# Optic_PWM.net
KiCad netlist of a schematic drawn in Altium Designer
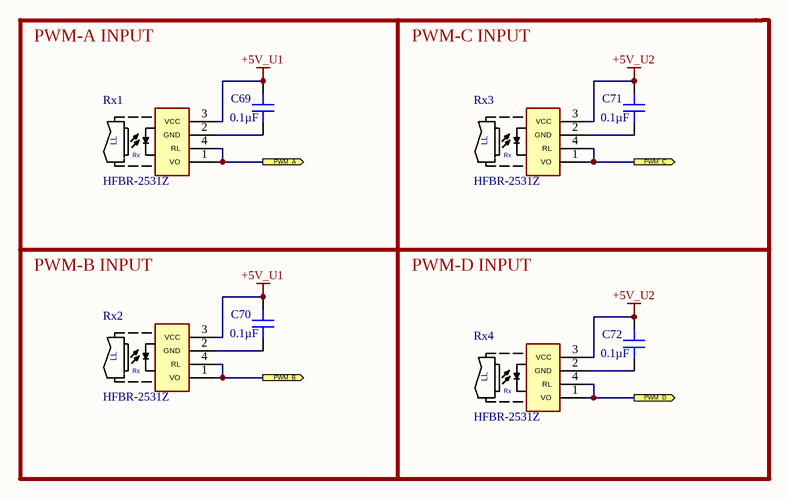
[diagram p0: Optic_PWM.SchDoc]

(export (version "E")
  (design (tool "Eeschema 10.0.6"))
  (components
    (comp (ref "C69")
      (value "0.1µF")
      (footprint "CAP 0603_1608")
      (description "CAP CER 0.1UF 50V X7R 0603")
      (fields (field (name "PART NUMBER") "C0603C104M5RACTU") (field (name "MANUFACTURER") "KEMET"))
      (libsource (lib "Celestial Altium Library - altium_library") (part "Capacitor"))
    )
    (comp (ref "C70")
      (value "0.1µF")
      (footprint "CAP 0603_1608")
      (description "CAP CER 0.1UF 50V X7R 0603")
      (fields (field (name "PART NUMBER") "C0603C104M5RACTU") (field (name "MANUFACTURER") "KEMET"))
      (libsource (lib "Celestial Altium Library - altium_library") (part "Capacitor"))
    )
    (comp (ref "C71")
      (value "0.1µF")
      (footprint "CAP 0603_1608")
      (description "CAP CER 0.1UF 50V X7R 0603")
      (fields (field (name "PART NUMBER") "C0603C104M5RACTU") (field (name "MANUFACTURER") "KEMET"))
      (libsource (lib "Celestial Altium Library - altium_library") (part "Capacitor"))
    )
    (comp (ref "C72")
      (value "0.1µF")
      (footprint "CAP 0603_1608")
      (description "CAP CER 0.1UF 50V X7R 0603")
      (fields (field (name "PART NUMBER") "C0603C104M5RACTU") (field (name "MANUFACTURER") "KEMET"))
      (libsource (lib "Celestial Altium Library - altium_library") (part "Capacitor"))
    )
    (comp (ref "Rx1")
      (value "HFBR-2531Z")
      (footprint "HFBR-15X1V")
      (description "RX Optical Fiber 5MBd 6-Pin")
      (fields (field (name "MANUFACTURER") "Broadcom Avago"))
      (libsource (lib "KasengLIb") (part "HFBR-2531Z"))
    )
    (comp (ref "Rx2")
      (value "HFBR-2531Z")
      (footprint "HFBR-15X1V")
      (description "RX Optical Fiber 5MBd 6-Pin")
      (fields (field (name "MANUFACTURER") "Broadcom Avago"))
      (libsource (lib "KasengLIb") (part "HFBR-2531Z"))
    )
    (comp (ref "Rx3")
      (value "HFBR-2531Z")
      (footprint "HFBR-15X1V")
      (description "RX Optical Fiber 5MBd 6-Pin")
      (fields (field (name "MANUFACTURER") "Broadcom Avago"))
      (libsource (lib "KasengLIb") (part "HFBR-2531Z"))
    )
    (comp (ref "Rx4")
      (value "HFBR-2531Z")
      (footprint "HFBR-15X1V")
      (description "RX Optical Fiber 5MBd 6-Pin")
      (fields (field (name "MANUFACTURER") "Broadcom Avago"))
      (libsource (lib "KasengLIb") (part "HFBR-2531Z"))
    )
  )
  (nets
    (net (code "1") (name "+5V_U1") (class "Default")
      (node (ref "C69") (pin "2") (pinfunction "2_2") (pintype "passive"))
      (node (ref "C70") (pin "2") (pinfunction "2_2") (pintype "passive"))
      (node (ref "Rx1") (pin "3") (pinfunction "VCC_3") (pintype "passive"))
      (node (ref "Rx2") (pin "3") (pinfunction "VCC_3") (pintype "passive"))
    )
    (net (code "2") (name "+5V_U2") (class "Default")
      (node (ref "C71") (pin "2") (pinfunction "2_2") (pintype "passive"))
      (node (ref "C72") (pin "2") (pinfunction "2_2") (pintype "passive"))
      (node (ref "Rx3") (pin "3") (pinfunction "VCC_3") (pintype "passive"))
      (node (ref "Rx4") (pin "3") (pinfunction "VCC_3") (pintype "passive"))
    )
    (net (code "3") (name "/PWM_A") (class "Default")
      (node (ref "Rx1") (pin "1") (pinfunction "VO_1") (pintype "passive"))
      (node (ref "Rx1") (pin "4") (pinfunction "RL_4") (pintype "passive"))
    )
    (net (code "4") (name "/PWM_B") (class "Default")
      (node (ref "Rx2") (pin "1") (pinfunction "VO_1") (pintype "passive"))
      (node (ref "Rx2") (pin "4") (pinfunction "RL_4") (pintype "passive"))
    )
    (net (code "5") (name "/PWM_C") (class "Default")
      (node (ref "Rx3") (pin "1") (pinfunction "VO_1") (pintype "passive"))
      (node (ref "Rx3") (pin "4") (pinfunction "RL_4") (pintype "passive"))
    )
    (net (code "6") (name "/PWM_D") (class "Default")
      (node (ref "Rx4") (pin "1") (pinfunction "VO_1") (pintype "passive"))
      (node (ref "Rx4") (pin "4") (pinfunction "RL_4") (pintype "passive"))
    )
    (net (code "7") (name "Net-(Rx1-GND)") (class "Default")
      (node (ref "C69") (pin "1") (pinfunction "1_1") (pintype "passive"))
      (node (ref "Rx1") (pin "2") (pinfunction "GND_2") (pintype "power_in"))
    )
    (net (code "8") (name "Net-(Rx2-GND)") (class "Default")
      (node (ref "C70") (pin "1") (pinfunction "1_1") (pintype "passive"))
      (node (ref "Rx2") (pin "2") (pinfunction "GND_2") (pintype "power_in"))
    )
    (net (code "9") (name "Net-(Rx3-GND)") (class "Default")
      (node (ref "C71") (pin "1") (pinfunction "1_1") (pintype "passive"))
      (node (ref "Rx3") (pin "2") (pinfunction "GND_2") (pintype "power_in"))
    )
    (net (code "10") (name "Net-(Rx4-GND)") (class "Default")
      (node (ref "C72") (pin "1") (pinfunction "1_1") (pintype "passive"))
      (node (ref "Rx4") (pin "2") (pinfunction "GND_2") (pintype "power_in"))
    )
  )
)
